# orient-beetle.net
KiCad netlist of a schematic drawn in EAGLE
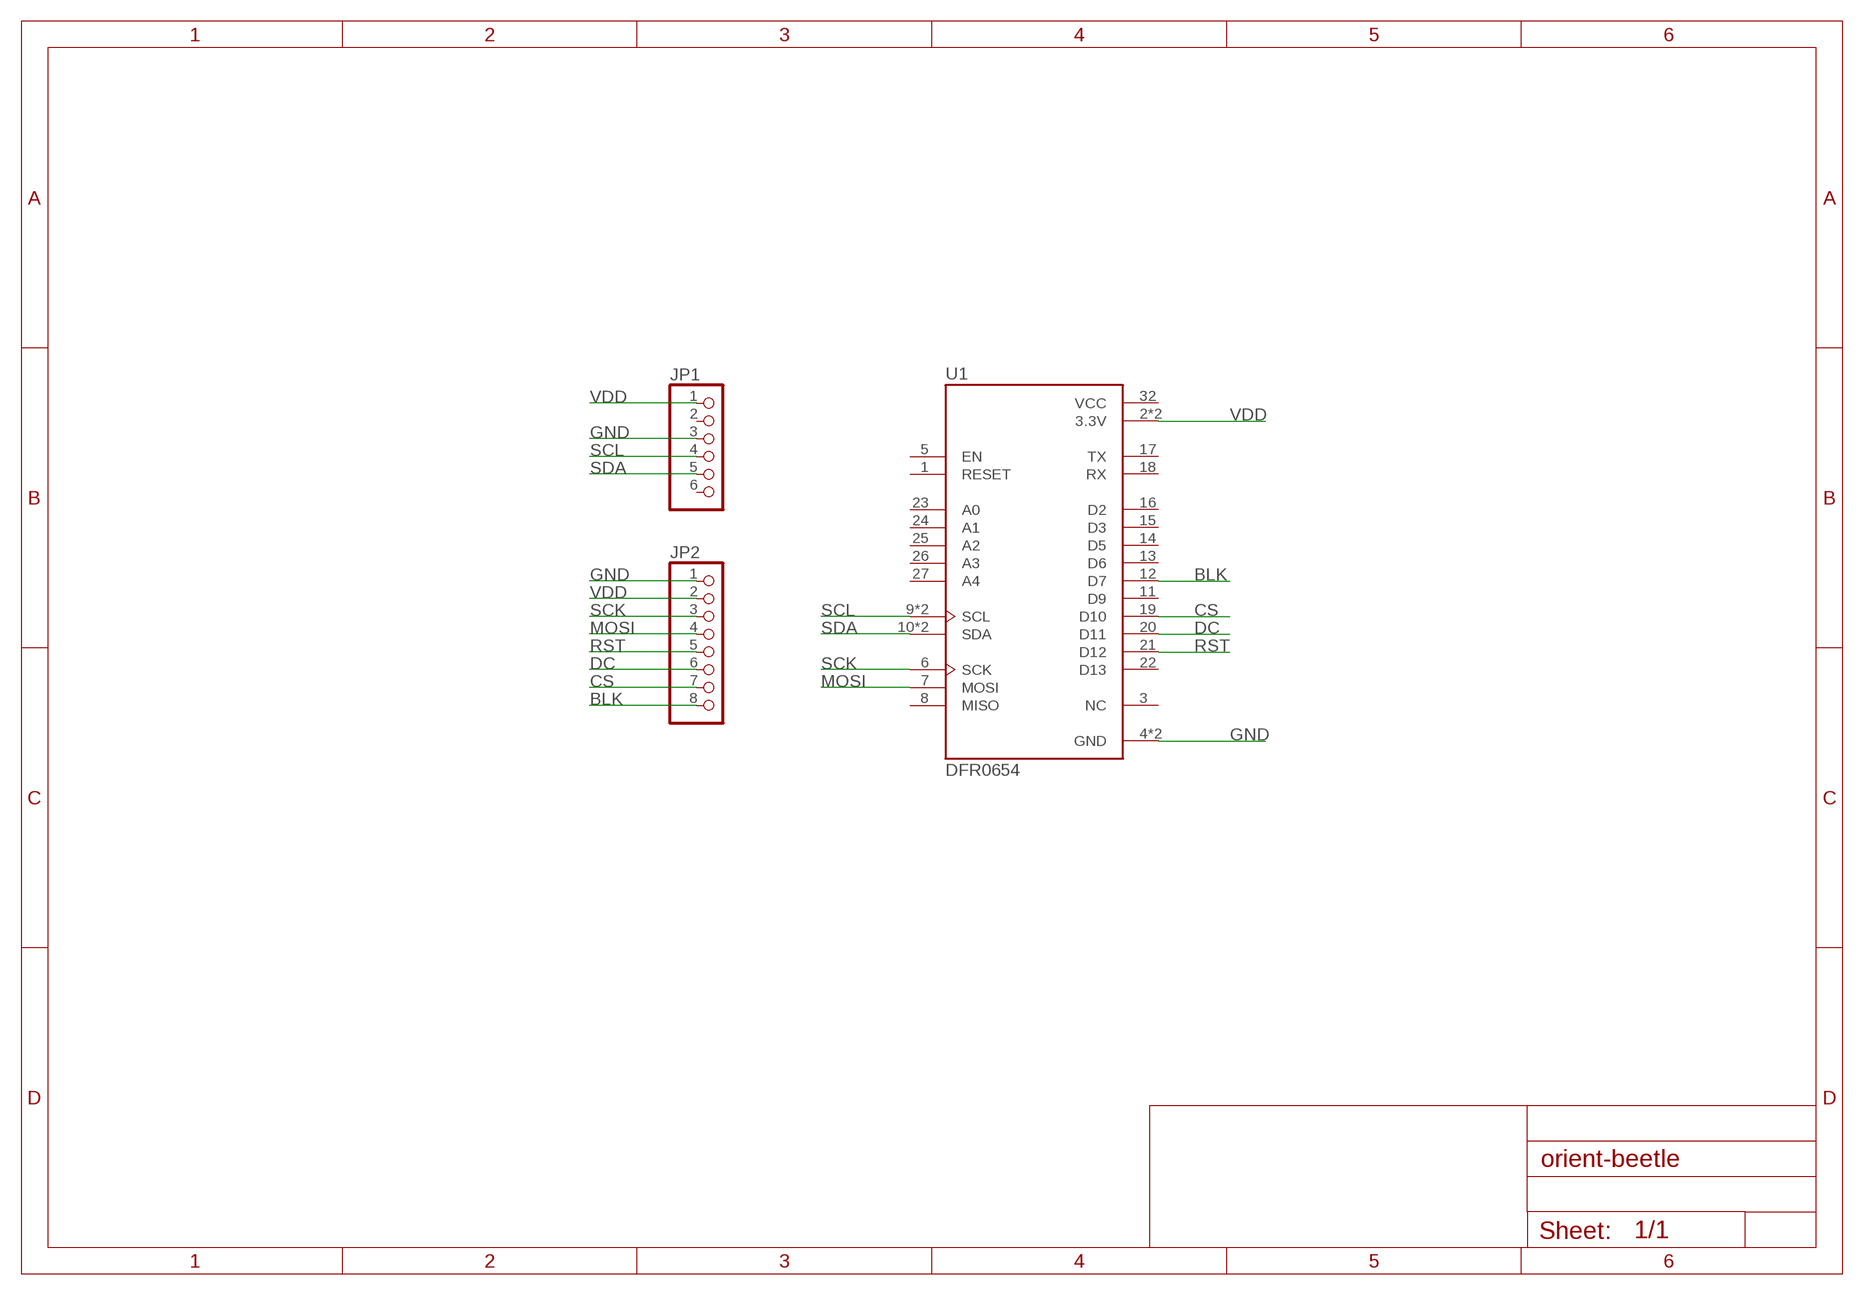
[diagram p0: schematic, sheet 1]

(export (version "E")
  (design (tool "Eeschema 10.0.6"))
  (components
    (comp (ref "JP1")
      (value "PINHD-1X6")
      (footprint "eagle-import:1X06")
      (libsource (lib "eagle-import") (part "PINHD-1X6"))
    )
    (comp (ref "JP2")
      (value "PINHD-1X8")
      (footprint "eagle-import:1X08")
      (libsource (lib "eagle-import") (part "PINHD-1X8"))
    )
    (comp (ref "U1")
      (value "DFR0654")
      (footprint "eagle-import:MODULE_DFR0654")
      (fields (field (name "MF") "DFRobot"))
      (libsource (lib "eagle-import") (part "DFR0654"))
    )
  )
  (nets
    (net (code "1") (name "/BLK") (class "Default")
      (node (ref "JP2") (pin "8") (pinfunction "8_8") (pintype "passive"))
      (node (ref "U1") (pin "12") (pinfunction "D7_12") (pintype "bidirectional"))
    )
    (net (code "2") (name "/CS") (class "Default")
      (node (ref "JP2") (pin "7") (pinfunction "7_7") (pintype "passive"))
      (node (ref "U1") (pin "19") (pinfunction "D10_19") (pintype "bidirectional"))
    )
    (net (code "3") (name "/DC") (class "Default")
      (node (ref "JP2") (pin "6") (pinfunction "6_6") (pintype "passive"))
      (node (ref "U1") (pin "20") (pinfunction "D11_20") (pintype "bidirectional"))
    )
    (net (code "4") (name "/GND") (class "Default")
      (node (ref "JP1") (pin "3") (pinfunction "3_3") (pintype "passive"))
      (node (ref "JP2") (pin "1") (pinfunction "1_1") (pintype "passive"))
      (node (ref "U1") (pin "30") (pinfunction "GND_30") (pintype "power_in"))
      (node (ref "U1") (pin "4") (pinfunction "GND_4") (pintype "power_in"))
    )
    (net (code "5") (name "/MOSI") (class "Default")
      (node (ref "JP2") (pin "4") (pinfunction "4_4") (pintype "passive"))
      (node (ref "U1") (pin "7") (pinfunction "MOSI_7") (pintype "input"))
    )
    (net (code "6") (name "/RST") (class "Default")
      (node (ref "JP2") (pin "5") (pinfunction "5_5") (pintype "passive"))
      (node (ref "U1") (pin "21") (pinfunction "D12_21") (pintype "bidirectional"))
    )
    (net (code "7") (name "/SCK") (class "Default")
      (node (ref "JP2") (pin "3") (pinfunction "3_3") (pintype "passive"))
      (node (ref "U1") (pin "6") (pinfunction "SCK_6") (pintype "input"))
    )
    (net (code "8") (name "/SCL") (class "Default")
      (node (ref "JP1") (pin "4") (pinfunction "4_4") (pintype "passive"))
      (node (ref "U1") (pin "29") (pinfunction "SCL_29") (pintype "input"))
      (node (ref "U1") (pin "9") (pinfunction "SCL_9") (pintype "input"))
    )
    (net (code "9") (name "/SDA") (class "Default")
      (node (ref "JP1") (pin "5") (pinfunction "5_5") (pintype "passive"))
      (node (ref "U1") (pin "10") (pinfunction "SDA_10") (pintype "bidirectional"))
      (node (ref "U1") (pin "28") (pinfunction "SDA_28") (pintype "bidirectional"))
    )
    (net (code "10") (name "/VCC") (class "Default")
      (node (ref "U1") (pin "32") (pinfunction "VCC_32") (pintype "power_in"))
    )
    (net (code "11") (name "/VDD") (class "Default")
      (node (ref "JP1") (pin "1") (pinfunction "1_1") (pintype "passive"))
      (node (ref "JP2") (pin "2") (pinfunction "2_2") (pintype "passive"))
      (node (ref "U1") (pin "2") (pinfunction "3.3V_2") (pintype "power_in"))
      (node (ref "U1") (pin "31") (pinfunction "3.3V_31") (pintype "power_in"))
    )
    (net (code "12") (name "unconnected-(JP1-Pad2)") (class "Default")
      (node (ref "JP1") (pin "2") (pinfunction "2_2") (pintype "passive"))
    )
    (net (code "13") (name "unconnected-(JP1-Pad6)") (class "Default")
      (node (ref "JP1") (pin "6") (pinfunction "6_6") (pintype "passive"))
    )
    (net (code "14") (name "unconnected-(U1-A0-Pad23)") (class "Default")
      (node (ref "U1") (pin "23") (pinfunction "A0_23") (pintype "input"))
    )
    (net (code "15") (name "unconnected-(U1-A1-Pad24)") (class "Default")
      (node (ref "U1") (pin "24") (pinfunction "A1_24") (pintype "input"))
    )
    (net (code "16") (name "unconnected-(U1-A2-Pad25)") (class "Default")
      (node (ref "U1") (pin "25") (pinfunction "A2_25") (pintype "input"))
    )
    (net (code "17") (name "unconnected-(U1-A3-Pad26)") (class "Default")
      (node (ref "U1") (pin "26") (pinfunction "A3_26") (pintype "input"))
    )
    (net (code "18") (name "unconnected-(U1-A4-Pad27)") (class "Default")
      (node (ref "U1") (pin "27") (pinfunction "A4_27") (pintype "input"))
    )
    (net (code "19") (name "unconnected-(U1-D2-Pad16)") (class "Default")
      (node (ref "U1") (pin "16") (pinfunction "D2_16") (pintype "bidirectional"))
    )
    (net (code "20") (name "unconnected-(U1-D3-Pad15)") (class "Default")
      (node (ref "U1") (pin "15") (pinfunction "D3_15") (pintype "bidirectional"))
    )
    (net (code "21") (name "unconnected-(U1-D5-Pad14)") (class "Default")
      (node (ref "U1") (pin "14") (pinfunction "D5_14") (pintype "bidirectional"))
    )
    (net (code "22") (name "unconnected-(U1-D6-Pad13)") (class "Default")
      (node (ref "U1") (pin "13") (pinfunction "D6_13") (pintype "bidirectional"))
    )
    (net (code "23") (name "unconnected-(U1-D9-Pad11)") (class "Default")
      (node (ref "U1") (pin "11") (pinfunction "D9_11") (pintype "bidirectional"))
    )
    (net (code "24") (name "unconnected-(U1-D13-Pad22)") (class "Default")
      (node (ref "U1") (pin "22") (pinfunction "D13_22") (pintype "bidirectional"))
    )
    (net (code "25") (name "unconnected-(U1-EN-Pad5)") (class "Default")
      (node (ref "U1") (pin "5") (pinfunction "EN_5") (pintype "input"))
    )
    (net (code "26") (name "unconnected-(U1-MISO-Pad8)") (class "Default")
      (node (ref "U1") (pin "8") (pinfunction "MISO_8") (pintype "output"))
    )
    (net (code "27") (name "unconnected-(U1-NC-Pad3)") (class "Default")
      (node (ref "U1") (pin "3") (pinfunction "NC_3") (pintype "no_connect"))
    )
    (net (code "28") (name "unconnected-(U1-RESET-Pad1)") (class "Default")
      (node (ref "U1") (pin "1") (pinfunction "RESET_1") (pintype "input"))
    )
    (net (code "29") (name "unconnected-(U1-RX-Pad18)") (class "Default")
      (node (ref "U1") (pin "18") (pinfunction "RX_18") (pintype "input"))
    )
    (net (code "30") (name "unconnected-(U1-TX-Pad17)") (class "Default")
      (node (ref "U1") (pin "17") (pinfunction "TX_17") (pintype "output"))
    )
  )
)
